# C.net
KiCad netlist of a schematic drawn in Altium Designer
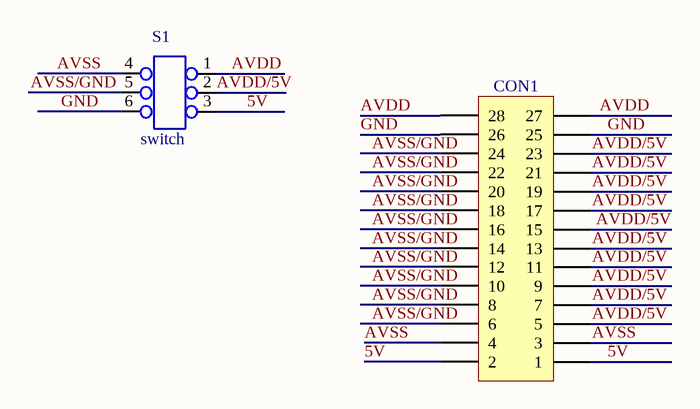
[diagram p0: C.SchDoc]

(export (version "E")
  (design (tool "Eeschema 10.0.6"))
  (components
    (comp (ref "CON1") (value "SV1") (footprint "26") (libsource (lib "C") (part "26")))
    (comp (ref "S1") (value "switch") (footprint "switch1") (libsource (lib "C") (part "switch 1")))
  )
  (nets
    (net (code "1") (name "/5V") (class "Default")
      (node (ref "CON1") (pin "1") (pinfunction "1_1") (pintype "passive"))
      (node (ref "CON1") (pin "2") (pinfunction "2_2") (pintype "passive"))
      (node (ref "S1") (pin "3") (pinfunction "3_3") (pintype "passive"))
    )
    (net (code "2") (name "/AVDD") (class "Default")
      (node (ref "CON1") (pin "27") (pinfunction "27_27") (pintype "passive"))
      (node (ref "CON1") (pin "28") (pinfunction "28_28") (pintype "passive"))
      (node (ref "S1") (pin "1") (pinfunction "1_1") (pintype "passive"))
    )
    (net (code "3") (name "/AVDD{slash}5V") (class "Default")
      (node (ref "CON1") (pin "11") (pinfunction "11_11") (pintype "passive"))
      (node (ref "CON1") (pin "13") (pinfunction "13_13") (pintype "passive"))
      (node (ref "CON1") (pin "15") (pinfunction "15_15") (pintype "passive"))
      (node (ref "CON1") (pin "17") (pinfunction "17_17") (pintype "passive"))
      (node (ref "CON1") (pin "19") (pinfunction "19_19") (pintype "passive"))
      (node (ref "CON1") (pin "21") (pinfunction "21_21") (pintype "passive"))
      (node (ref "CON1") (pin "23") (pinfunction "23_23") (pintype "passive"))
      (node (ref "CON1") (pin "5") (pinfunction "5_5") (pintype "passive"))
      (node (ref "CON1") (pin "7") (pinfunction "7_7") (pintype "passive"))
      (node (ref "CON1") (pin "9") (pinfunction "9_9") (pintype "passive"))
      (node (ref "S1") (pin "2") (pinfunction "2_2") (pintype "passive"))
    )
    (net (code "4") (name "/AVSS") (class "Default")
      (node (ref "CON1") (pin "3") (pinfunction "3_3") (pintype "passive"))
      (node (ref "CON1") (pin "4") (pinfunction "4_4") (pintype "passive"))
      (node (ref "S1") (pin "4") (pinfunction "4_4") (pintype "passive"))
    )
    (net (code "5") (name "/AVSS{slash}GND") (class "Default")
      (node (ref "CON1") (pin "10") (pinfunction "10_10") (pintype "passive"))
      (node (ref "CON1") (pin "12") (pinfunction "12_12") (pintype "passive"))
      (node (ref "CON1") (pin "14") (pinfunction "14_14") (pintype "passive"))
      (node (ref "CON1") (pin "16") (pinfunction "16_16") (pintype "passive"))
      (node (ref "CON1") (pin "18") (pinfunction "18_18") (pintype "passive"))
      (node (ref "CON1") (pin "20") (pinfunction "20_20") (pintype "passive"))
      (node (ref "CON1") (pin "22") (pinfunction "22_22") (pintype "passive"))
      (node (ref "CON1") (pin "24") (pinfunction "24_24") (pintype "passive"))
      (node (ref "CON1") (pin "6") (pinfunction "6_6") (pintype "passive"))
      (node (ref "CON1") (pin "8") (pinfunction "8_8") (pintype "passive"))
      (node (ref "S1") (pin "5") (pinfunction "5_5") (pintype "passive"))
    )
    (net (code "6") (name "/GND") (class "Default")
      (node (ref "CON1") (pin "25") (pinfunction "25_25") (pintype "passive"))
      (node (ref "CON1") (pin "26") (pinfunction "26_26") (pintype "passive"))
      (node (ref "S1") (pin "6") (pinfunction "6_6") (pintype "passive"))
    )
  )
)
